# breakout1.net
KiCad netlist of a schematic drawn in EAGLE
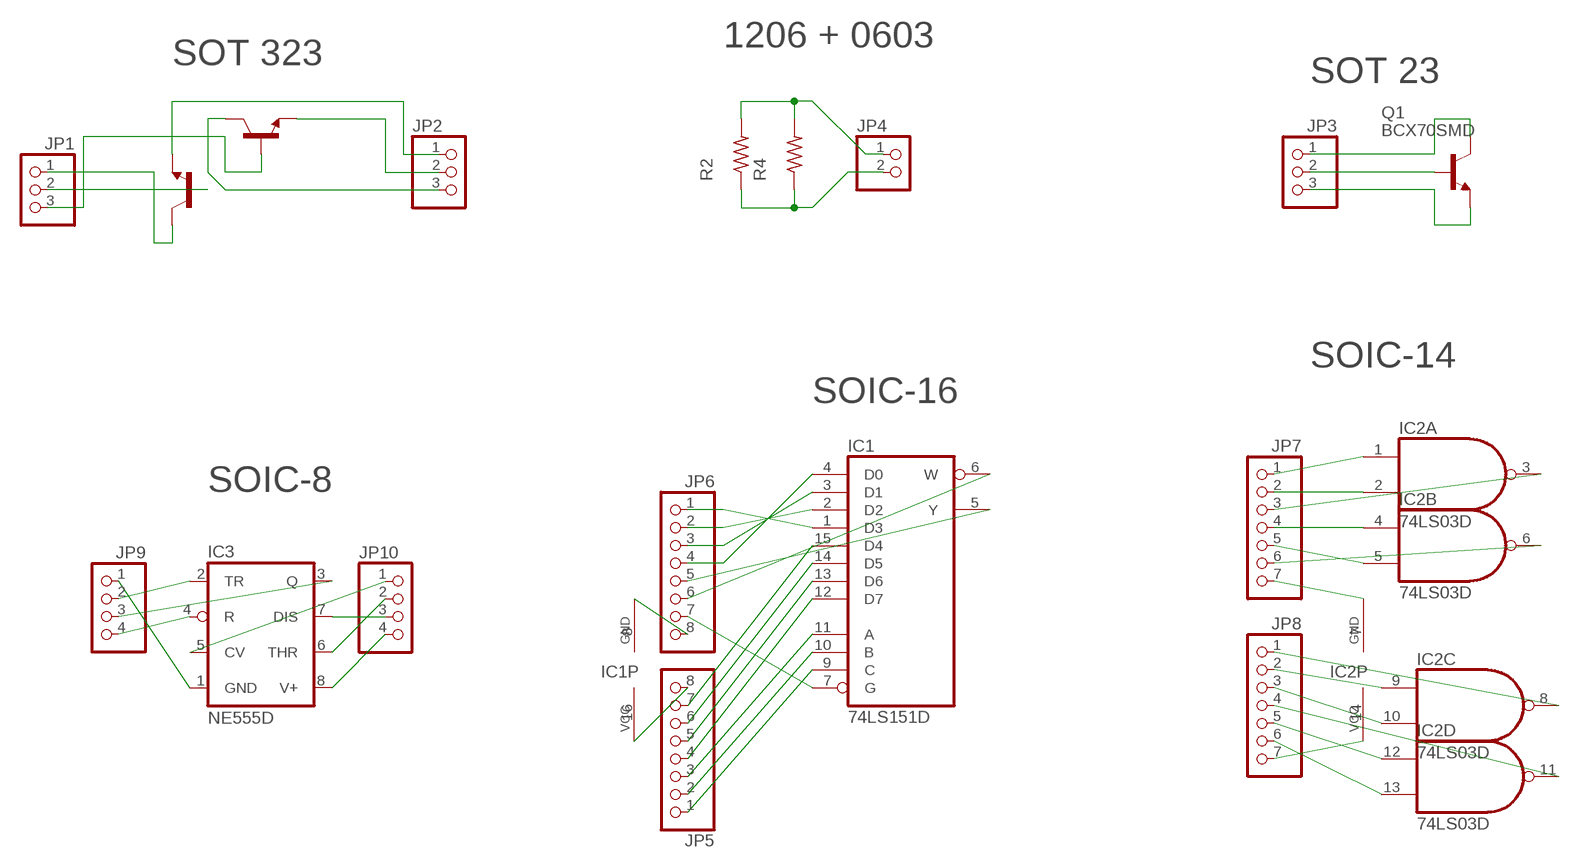
[diagram p0: schematic, sheet 1]

(export (version "E")
  (design (tool "Eeschema 10.0.6"))
  (components
    (comp (ref "IC1")
      (value "74LS151D")
      (footprint "eagle-import:SO16")
      (libsource (lib "eagle-import") (part "74151DLS"))
    )
    (comp (ref "IC2")
      (value "74LS03D")
      (footprint "eagle-import:SO14")
      (libsource (lib "eagle-import") (part "7403DLS"))
    )
    (comp (ref "IC3")
      (value "NE555D")
      (footprint "eagle-import:SO08")
      (libsource (lib "eagle-import") (part "555DNE"))
    )
    (comp (ref "JP1")
      (value "PINHD-1X3")
      (footprint "eagle-import:1X03")
      (libsource (lib "eagle-import") (part "PINHD-1X3"))
    )
    (comp (ref "JP2")
      (value "PINHD-1X3")
      (footprint "eagle-import:1X03")
      (libsource (lib "eagle-import") (part "PINHD-1X3"))
    )
    (comp (ref "JP3")
      (value "PINHD-1X3")
      (footprint "eagle-import:1X03")
      (libsource (lib "eagle-import") (part "PINHD-1X3"))
    )
    (comp (ref "JP4")
      (value "PINHD-1X2")
      (footprint "eagle-import:1X02")
      (libsource (lib "eagle-import") (part "PINHD-1X2"))
    )
    (comp (ref "JP5")
      (value "PINHD-1X8")
      (footprint "eagle-import:1X08")
      (libsource (lib "eagle-import") (part "PINHD-1X8"))
    )
    (comp (ref "JP6")
      (value "PINHD-1X8")
      (footprint "eagle-import:1X08")
      (libsource (lib "eagle-import") (part "PINHD-1X8"))
    )
    (comp (ref "JP7")
      (value "PINHD-1X7")
      (footprint "eagle-import:1X07")
      (libsource (lib "eagle-import") (part "PINHD-1X7"))
    )
    (comp (ref "JP8")
      (value "PINHD-1X7")
      (footprint "eagle-import:1X07")
      (libsource (lib "eagle-import") (part "PINHD-1X7"))
    )
    (comp (ref "JP9")
      (value "PINHD-1X4")
      (footprint "eagle-import:1X04")
      (libsource (lib "eagle-import") (part "PINHD-1X4"))
    )
    (comp (ref "JP10")
      (value "PINHD-1X4")
      (footprint "eagle-import:1X04")
      (libsource (lib "eagle-import") (part "PINHD-1X4"))
    )
    (comp (ref "Q1")
      (value "BCX70SMD")
      (footprint "eagle-import:SOT23")
      (libsource (lib "eagle-import") (part "BCX70SMD"))
    )
    (comp (ref "R2")
      (value "R-US_R0603")
      (footprint "eagle-import:R0603")
      (libsource (lib "eagle-import") (part "R-US_R0603"))
    )
    (comp (ref "R4")
      (value "R-US_R1206")
      (footprint "eagle-import:R1206")
      (libsource (lib "eagle-import") (part "R-US_R1206"))
    )
    (comp (ref "U$1")
      (value "DMMT3904W")
      (footprint "eagle-import:SOT363")
      (libsource (lib "eagle-import") (part "DMMT3904W"))
    )
  )
  (nets
    (net (code "1") (name "Net-(IC1A-A)") (class "Default")
      (node (ref "IC1") (pin "11") (pinfunction "A_11") (pintype "input"))
      (node (ref "JP5") (pin "3") (pinfunction "3_3") (pintype "passive"))
    )
    (net (code "2") (name "Net-(IC1A-B)") (class "Default")
      (node (ref "IC1") (pin "10") (pinfunction "B_10") (pintype "input"))
      (node (ref "JP5") (pin "2") (pinfunction "2_2") (pintype "passive"))
    )
    (net (code "3") (name "Net-(IC1A-C)") (class "Default")
      (node (ref "IC1") (pin "9") (pinfunction "C_9") (pintype "input"))
      (node (ref "JP5") (pin "1") (pinfunction "1_1") (pintype "passive"))
    )
    (net (code "4") (name "Net-(IC1A-D0)") (class "Default")
      (node (ref "IC1") (pin "4") (pinfunction "D0_4") (pintype "input"))
      (node (ref "JP6") (pin "4") (pinfunction "4_4") (pintype "passive"))
    )
    (net (code "5") (name "Net-(IC1A-D1)") (class "Default")
      (node (ref "IC1") (pin "3") (pinfunction "D1_3") (pintype "input"))
      (node (ref "JP6") (pin "3") (pinfunction "3_3") (pintype "passive"))
    )
    (net (code "6") (name "Net-(IC1A-D2)") (class "Default")
      (node (ref "IC1") (pin "2") (pinfunction "D2_2") (pintype "input"))
      (node (ref "JP6") (pin "2") (pinfunction "2_2") (pintype "passive"))
    )
    (net (code "7") (name "Net-(IC1A-D3)") (class "Default")
      (node (ref "IC1") (pin "1") (pinfunction "D3_1") (pintype "input"))
      (node (ref "JP6") (pin "1") (pinfunction "1_1") (pintype "passive"))
    )
    (net (code "8") (name "Net-(IC1A-D4)") (class "Default")
      (node (ref "IC1") (pin "15") (pinfunction "D4_15") (pintype "input"))
      (node (ref "JP5") (pin "7") (pinfunction "7_7") (pintype "passive"))
    )
    (net (code "9") (name "Net-(IC1A-D5)") (class "Default")
      (node (ref "IC1") (pin "14") (pinfunction "D5_14") (pintype "input"))
      (node (ref "JP5") (pin "6") (pinfunction "6_6") (pintype "passive"))
    )
    (net (code "10") (name "Net-(IC1A-D6)") (class "Default")
      (node (ref "IC1") (pin "13") (pinfunction "D6_13") (pintype "input"))
      (node (ref "JP5") (pin "5") (pinfunction "5_5") (pintype "passive"))
    )
    (net (code "11") (name "Net-(IC1A-D7)") (class "Default")
      (node (ref "IC1") (pin "12") (pinfunction "D7_12") (pintype "input"))
      (node (ref "JP5") (pin "4") (pinfunction "4_4") (pintype "passive"))
    )
    (net (code "12") (name "Net-(IC1A-G)") (class "Default")
      (node (ref "IC1") (pin "7") (pinfunction "G_7") (pintype "input"))
      (node (ref "JP6") (pin "7") (pinfunction "7_7") (pintype "passive"))
    )
    (net (code "13") (name "Net-(IC1A-W)") (class "Default")
      (node (ref "IC1") (pin "6") (pinfunction "W_6") (pintype "output"))
      (node (ref "JP6") (pin "6") (pinfunction "6_6") (pintype "passive"))
    )
    (net (code "14") (name "Net-(IC1A-Y)") (class "Default")
      (node (ref "IC1") (pin "5") (pinfunction "Y_5") (pintype "output"))
      (node (ref "JP6") (pin "5") (pinfunction "5_5") (pintype "passive"))
    )
    (net (code "15") (name "Net-(IC1B-GND)") (class "Default")
      (node (ref "IC1") (pin "8") (pinfunction "GND_8") (pintype "power_in"))
      (node (ref "JP6") (pin "8") (pinfunction "8_8") (pintype "passive"))
    )
    (net (code "16") (name "Net-(IC1B-VCC)") (class "Default")
      (node (ref "IC1") (pin "16") (pinfunction "VCC_16") (pintype "power_in"))
      (node (ref "JP5") (pin "8") (pinfunction "8_8") (pintype "passive"))
    )
    (net (code "17") (name "Net-(IC2A-I0)") (class "Default")
      (node (ref "IC2") (pin "1") (pinfunction "I0_1") (pintype "input"))
      (node (ref "JP7") (pin "1") (pinfunction "1_1") (pintype "passive"))
    )
    (net (code "18") (name "Net-(IC2A-I1)") (class "Default")
      (node (ref "IC2") (pin "2") (pinfunction "I1_2") (pintype "input"))
      (node (ref "JP7") (pin "2") (pinfunction "2_2") (pintype "passive"))
    )
    (net (code "19") (name "Net-(IC2A-O)") (class "Default")
      (node (ref "IC2") (pin "3") (pinfunction "O_3") (pintype "open_collector"))
      (node (ref "JP7") (pin "3") (pinfunction "3_3") (pintype "passive"))
    )
    (net (code "20") (name "Net-(IC2B-I0)") (class "Default")
      (node (ref "IC2") (pin "4") (pinfunction "I0_4") (pintype "input"))
      (node (ref "JP7") (pin "4") (pinfunction "4_4") (pintype "passive"))
    )
    (net (code "21") (name "Net-(IC2B-I1)") (class "Default")
      (node (ref "IC2") (pin "5") (pinfunction "I1_5") (pintype "input"))
      (node (ref "JP7") (pin "5") (pinfunction "5_5") (pintype "passive"))
    )
    (net (code "22") (name "Net-(IC2B-O)") (class "Default")
      (node (ref "IC2") (pin "6") (pinfunction "O_6") (pintype "open_collector"))
      (node (ref "JP7") (pin "6") (pinfunction "6_6") (pintype "passive"))
    )
    (net (code "23") (name "Net-(IC2C-I0)") (class "Default")
      (node (ref "IC2") (pin "9") (pinfunction "I0_9") (pintype "input"))
      (node (ref "JP8") (pin "2") (pinfunction "2_2") (pintype "passive"))
    )
    (net (code "24") (name "Net-(IC2C-I1)") (class "Default")
      (node (ref "IC2") (pin "10") (pinfunction "I1_10") (pintype "input"))
      (node (ref "JP8") (pin "3") (pinfunction "3_3") (pintype "passive"))
    )
    (net (code "25") (name "Net-(IC2C-O)") (class "Default")
      (node (ref "IC2") (pin "8") (pinfunction "O_8") (pintype "open_collector"))
      (node (ref "JP8") (pin "1") (pinfunction "1_1") (pintype "passive"))
    )
    (net (code "26") (name "Net-(IC2D-I0)") (class "Default")
      (node (ref "IC2") (pin "12") (pinfunction "I0_12") (pintype "input"))
      (node (ref "JP8") (pin "5") (pinfunction "5_5") (pintype "passive"))
    )
    (net (code "27") (name "Net-(IC2D-I1)") (class "Default")
      (node (ref "IC2") (pin "13") (pinfunction "I1_13") (pintype "input"))
      (node (ref "JP8") (pin "6") (pinfunction "6_6") (pintype "passive"))
    )
    (net (code "28") (name "Net-(IC2D-O)") (class "Default")
      (node (ref "IC2") (pin "11") (pinfunction "O_11") (pintype "open_collector"))
      (node (ref "JP8") (pin "4") (pinfunction "4_4") (pintype "passive"))
    )
    (net (code "29") (name "Net-(IC2E-GND)") (class "Default")
      (node (ref "IC2") (pin "7") (pinfunction "GND_7") (pintype "power_in"))
      (node (ref "JP7") (pin "7") (pinfunction "7_7") (pintype "passive"))
    )
    (net (code "30") (name "Net-(IC2E-VCC)") (class "Default")
      (node (ref "IC2") (pin "14") (pinfunction "VCC_14") (pintype "power_in"))
      (node (ref "JP8") (pin "7") (pinfunction "7_7") (pintype "passive"))
    )
    (net (code "31") (name "Net-(IC3-CV)") (class "Default")
      (node (ref "IC3") (pin "5") (pinfunction "CV_5") (pintype "input"))
      (node (ref "JP10") (pin "1") (pinfunction "1_1") (pintype "passive"))
    )
    (net (code "32") (name "Net-(IC3-DIS)") (class "Default")
      (node (ref "IC3") (pin "7") (pinfunction "DIS_7") (pintype "input"))
      (node (ref "JP10") (pin "3") (pinfunction "3_3") (pintype "passive"))
    )
    (net (code "33") (name "Net-(IC3-GND)") (class "Default")
      (node (ref "IC3") (pin "1") (pinfunction "GND_1") (pintype "power_in"))
      (node (ref "JP9") (pin "1") (pinfunction "1_1") (pintype "passive"))
    )
    (net (code "34") (name "Net-(IC3-Q)") (class "Default")
      (node (ref "IC3") (pin "3") (pinfunction "Q_3") (pintype "output"))
      (node (ref "JP9") (pin "3") (pinfunction "3_3") (pintype "passive"))
    )
    (net (code "35") (name "Net-(IC3-R)") (class "Default")
      (node (ref "IC3") (pin "4") (pinfunction "R_4") (pintype "input"))
      (node (ref "JP9") (pin "4") (pinfunction "4_4") (pintype "passive"))
    )
    (net (code "36") (name "Net-(IC3-THR)") (class "Default")
      (node (ref "IC3") (pin "6") (pinfunction "THR_6") (pintype "input"))
      (node (ref "JP10") (pin "2") (pinfunction "2_2") (pintype "passive"))
    )
    (net (code "37") (name "Net-(IC3-TR)") (class "Default")
      (node (ref "IC3") (pin "2") (pinfunction "TR_2") (pintype "input"))
      (node (ref "JP9") (pin "2") (pinfunction "2_2") (pintype "passive"))
    )
    (net (code "38") (name "Net-(IC3-V+)") (class "Default")
      (node (ref "IC3") (pin "8") (pinfunction "V+_8") (pintype "power_in"))
      (node (ref "JP10") (pin "4") (pinfunction "4_4") (pintype "passive"))
    )
    (net (code "39") (name "Net-(JP4-Pad1)") (class "Default")
      (node (ref "JP4") (pin "1") (pinfunction "1_1") (pintype "passive"))
      (node (ref "R2") (pin "2") (pinfunction "2_2") (pintype "passive"))
      (node (ref "R4") (pin "2") (pinfunction "2_2") (pintype "passive"))
    )
    (net (code "40") (name "Net-(JP4-Pad2)") (class "Default")
      (node (ref "JP4") (pin "2") (pinfunction "2_2") (pintype "passive"))
      (node (ref "R2") (pin "1") (pinfunction "1_1") (pintype "passive"))
      (node (ref "R4") (pin "1") (pinfunction "1_1") (pintype "passive"))
    )
    (net (code "41") (name "Net-(Q1-B)") (class "Default")
      (node (ref "JP3") (pin "2") (pinfunction "2_2") (pintype "passive"))
      (node (ref "Q1") (pin "1") (pinfunction "B_1") (pintype "passive"))
    )
    (net (code "42") (name "Net-(Q1-C)") (class "Default")
      (node (ref "JP3") (pin "1") (pinfunction "1_1") (pintype "passive"))
      (node (ref "Q1") (pin "3") (pinfunction "C_3") (pintype "passive"))
    )
    (net (code "43") (name "Net-(Q1-E)") (class "Default")
      (node (ref "JP3") (pin "3") (pinfunction "3_3") (pintype "passive"))
      (node (ref "Q1") (pin "2") (pinfunction "E_2") (pintype "passive"))
    )
    (net (code "44") (name "Net-(U$1A-B)") (class "Default")
      (node (ref "JP1") (pin "3") (pinfunction "3_3") (pintype "passive"))
      (node (ref "U$1") (pin "1") (pinfunction "B_1") (pintype "passive"))
    )
    (net (code "45") (name "Net-(U$1A-C)") (class "Default")
      (node (ref "JP2") (pin "3") (pinfunction "3_3") (pintype "passive"))
      (node (ref "U$1") (pin "6") (pinfunction "C_6") (pintype "passive"))
    )
    (net (code "46") (name "Net-(U$1A-E)") (class "Default")
      (node (ref "JP2") (pin "2") (pinfunction "2_2") (pintype "passive"))
      (node (ref "U$1") (pin "5") (pinfunction "E_5") (pintype "passive"))
    )
    (net (code "47") (name "Net-(U$1B-B)") (class "Default")
      (node (ref "JP1") (pin "2") (pinfunction "2_2") (pintype "passive"))
      (node (ref "U$1") (pin "2") (pinfunction "B_2") (pintype "passive"))
    )
    (net (code "48") (name "Net-(U$1B-C)") (class "Default")
      (node (ref "JP1") (pin "1") (pinfunction "1_1") (pintype "passive"))
      (node (ref "U$1") (pin "3") (pinfunction "C_3") (pintype "passive"))
    )
    (net (code "49") (name "Net-(U$1B-E)") (class "Default")
      (node (ref "JP2") (pin "1") (pinfunction "1_1") (pintype "passive"))
      (node (ref "U$1") (pin "4") (pinfunction "E_4") (pintype "passive"))
    )
  )
)
